# beaconv09.net
KiCad netlist of a schematic drawn in EAGLE
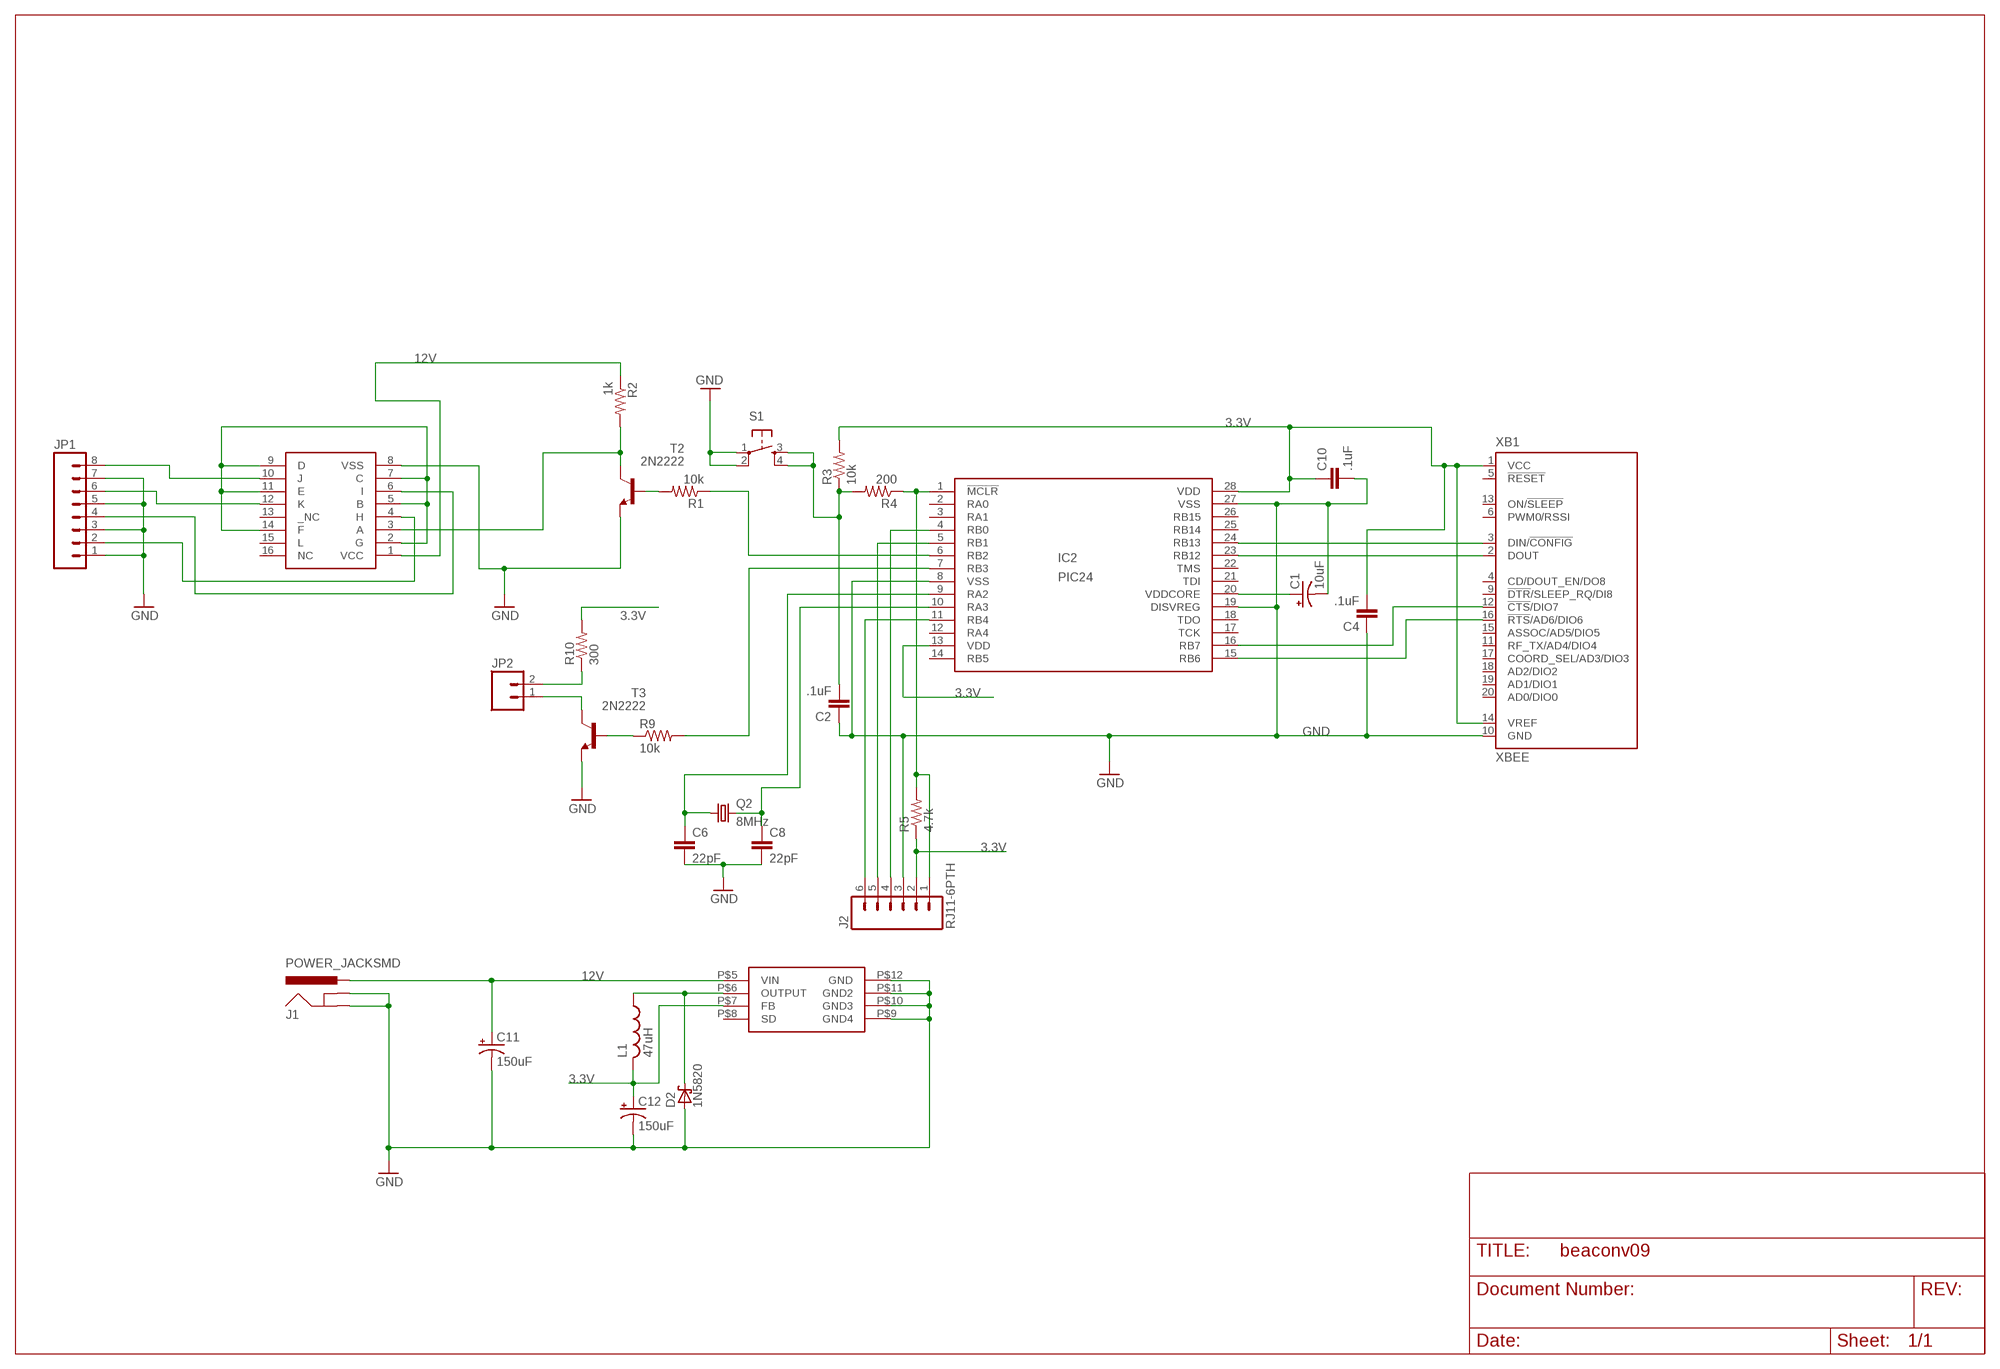
[diagram p0: schematic, sheet 1]

(export (version "E")
  (design (tool "Eeschema 10.0.6"))
  (components
    (comp (ref "AP1509")
      (value "BUCK1")
      (footprint "eagle-import:BUCK")
      (libsource (lib "eagle-import") (part "BUCK1"))
    )
    (comp (ref "C1")
      (value "10uF")
      (footprint "eagle-import:EIA3216")
      (libsource (lib "eagle-import") (part "CAP_POL1206"))
    )
    (comp (ref "C2")
      (value ".1uF")
      (footprint "eagle-import:C1206")
      (libsource (lib "eagle-import") (part "C-EUC1206"))
    )
    (comp (ref "C4")
      (value ".1uF")
      (footprint "eagle-import:C1206")
      (libsource (lib "eagle-import") (part "C-EUC1206"))
    )
    (comp (ref "C6")
      (value "22pF")
      (footprint "eagle-import:C1206")
      (libsource (lib "eagle-import") (part "C-EUC1206"))
    )
    (comp (ref "C8")
      (value "22pF")
      (footprint "eagle-import:C1206")
      (libsource (lib "eagle-import") (part "C-EUC1206"))
    )
    (comp (ref "C10")
      (value ".1uF")
      (footprint "eagle-import:C1206")
      (libsource (lib "eagle-import") (part "C-EUC1206"))
    )
    (comp (ref "C11")
      (value "150uF")
      (footprint "eagle-import:ECAPSMPS")
      (libsource (lib "eagle-import") (part "CAP_POL"))
    )
    (comp (ref "C12")
      (value "150uF")
      (footprint "eagle-import:ECAPSMPS")
      (libsource (lib "eagle-import") (part "CAP_POL"))
    )
    (comp (ref "D2")
      (value "1N5820")
      (footprint "eagle-import:DO201T15")
      (libsource (lib "eagle-import") (part "15KEXXD"))
    )
    (comp (ref "IC2")
      (value "PIC24")
      (footprint "eagle-import:SO28W")
      (libsource (lib "eagle-import") (part "PIC24FJ16GA002"))
    )
    (comp (ref "J1")
      (value "POWER_JACKSMD")
      (footprint "eagle-import:POWER_JACK_SMD")
      (libsource (lib "eagle-import") (part "POWER_JACKSMD"))
    )
    (comp (ref "J2")
      (value "RJ11-6PTH")
      (footprint "eagle-import:RJ11-6")
      (libsource (lib "eagle-import") (part "RJ11-6PTH"))
    )
    (comp (ref "JP1")
      (value "M08LOCK")
      (footprint "eagle-import:1X08_LOCK")
      (libsource (lib "eagle-import") (part "M08LOCK"))
    )
    (comp (ref "JP2")
      (value "M02LOCK")
      (footprint "eagle-import:1X02_LOCK")
      (libsource (lib "eagle-import") (part "M02LOCK"))
    )
    (comp (ref "L1")
      (value "47uH")
      (footprint "eagle-import:BUCKINDUCTOR2")
      (libsource (lib "eagle-import") (part "BUCKINDUCTOR"))
    )
    (comp (ref "Q2")
      (value "8MHz")
      (footprint "eagle-import:HC49UP")
      (libsource (lib "eagle-import") (part "CRYSTALHC49UP"))
    )
    (comp (ref "R1")
      (value "10k")
      (footprint "eagle-import:1206")
      (libsource (lib "eagle-import") (part "RESISTOR1206"))
    )
    (comp (ref "R2")
      (value "1k")
      (footprint "eagle-import:1206")
      (libsource (lib "eagle-import") (part "RESISTOR1206"))
    )
    (comp (ref "R3")
      (value "10k")
      (footprint "eagle-import:1206")
      (libsource (lib "eagle-import") (part "RESISTOR1206"))
    )
    (comp (ref "R4")
      (value "200")
      (footprint "eagle-import:1206")
      (libsource (lib "eagle-import") (part "RESISTOR1206"))
    )
    (comp (ref "R5")
      (value "4.7k")
      (footprint "eagle-import:R1206")
      (libsource (lib "eagle-import") (part "R-US_R1206"))
    )
    (comp (ref "R9")
      (value "10k")
      (footprint "eagle-import:R1206")
      (libsource (lib "eagle-import") (part "R-US_R1206"))
    )
    (comp (ref "R10")
      (value "300")
      (footprint "eagle-import:R1206")
      (libsource (lib "eagle-import") (part "R-US_R1206"))
    )
    (comp (ref "S1")
      (value "TAC_SWITCHSMD")
      (footprint "eagle-import:TACTILE_SWITCH_SMD")
      (libsource (lib "eagle-import") (part "TAC_SWITCHSMD"))
    )
    (comp (ref "T2")
      (value "2N2222")
      (footprint "eagle-import:TO92-CBE")
      (libsource (lib "eagle-import") (part "2N2222"))
    )
    (comp (ref "T3")
      (value "2N2222")
      (footprint "eagle-import:TO92-CBE")
      (libsource (lib "eagle-import") (part "2N2222"))
    )
    (comp (ref "U$2")
      (value "CD4049")
      (footprint "eagle-import:DIL16")
      (libsource (lib "eagle-import") (part "CD4049"))
    )
    (comp (ref "XB1")
      (value "XBEE")
      (footprint "eagle-import:XBEE")
      (fields (field (name "MPN") "XBP24-Z7UIT-004"))
      (libsource (lib "eagle-import") (part "XBEE"))
    )
  )
  (nets
    (net (code "1") (name "/3.3V") (class "Default")
      (node (ref "AP1509") (pin "P$7") (pinfunction "FB_P$7") (pintype "bidirectional"))
      (node (ref "C10") (pin "1") (pinfunction "1_1") (pintype "passive"))
      (node (ref "C12") (pin "P$1") (pinfunction "+_P$1") (pintype "passive"))
      (node (ref "C4") (pin "2") (pinfunction "2_2") (pintype "passive"))
      (node (ref "IC2") (pin "13") (pinfunction "VDD_13") (pintype "power_in"))
      (node (ref "IC2") (pin "28") (pinfunction "VDD_28") (pintype "power_in"))
      (node (ref "J2") (pin "2") (pinfunction "2_2") (pintype "passive"))
      (node (ref "L1") (pin "P$2") (pinfunction "2_P$2") (pintype "passive"))
      (node (ref "R10") (pin "2") (pinfunction "2_2") (pintype "passive"))
      (node (ref "R3") (pin "2") (pinfunction "2_2") (pintype "passive"))
      (node (ref "R5") (pin "1") (pinfunction "1_1") (pintype "passive"))
      (node (ref "XB1") (pin "1") (pinfunction "VCC_1") (pintype "power_in"))
      (node (ref "XB1") (pin "14") (pinfunction "VREF_14") (pintype "input"))
    )
    (net (code "2") (name "/12V") (class "Default")
      (node (ref "AP1509") (pin "P$5") (pinfunction "VIN_P$5") (pintype "bidirectional"))
      (node (ref "C11") (pin "P$1") (pinfunction "+_P$1") (pintype "passive"))
      (node (ref "J1") (pin "VIN0") (pinfunction "PWR_VIN0") (pintype "bidirectional"))
      (node (ref "R2") (pin "1") (pinfunction "1_1") (pintype "passive"))
      (node (ref "U$2") (pin "1") (pinfunction "VCC_1") (pintype "bidirectional"))
    )
    (net (code "3") (name "GND") (class "Default")
      (node (ref "AP1509") (pin "P$10") (pinfunction "GND3_P$10") (pintype "bidirectional"))
      (node (ref "AP1509") (pin "P$11") (pinfunction "GND2_P$11") (pintype "bidirectional"))
      (node (ref "AP1509") (pin "P$12") (pinfunction "GND_P$12") (pintype "bidirectional"))
      (node (ref "AP1509") (pin "P$9") (pinfunction "GND4_P$9") (pintype "bidirectional"))
      (node (ref "C1") (pin "C") (pinfunction "-_C") (pintype "passive"))
      (node (ref "C10") (pin "2") (pinfunction "2_2") (pintype "passive"))
      (node (ref "C11") (pin "P$2") (pinfunction "-_P$2") (pintype "passive"))
      (node (ref "C12") (pin "P$2") (pinfunction "-_P$2") (pintype "passive"))
      (node (ref "C2") (pin "1") (pinfunction "1_1") (pintype "passive"))
      (node (ref "C4") (pin "1") (pinfunction "1_1") (pintype "passive"))
      (node (ref "C6") (pin "2") (pinfunction "2_2") (pintype "passive"))
      (node (ref "C8") (pin "2") (pinfunction "2_2") (pintype "passive"))
      (node (ref "D2") (pin "A") (pinfunction "A_A") (pintype "passive"))
      (node (ref "IC2") (pin "19") (pinfunction "DISVREG_19") (pintype "passive"))
      (node (ref "IC2") (pin "27") (pinfunction "VSS_27") (pintype "power_in"))
      (node (ref "IC2") (pin "8") (pinfunction "VSS_8") (pintype "power_in"))
      (node (ref "J1") (pin "GND") (pinfunction "GNDBREAK_GND") (pintype "bidirectional"))
      (node (ref "J1") (pin "P$4") (pinfunction "GND_P$4") (pintype "bidirectional"))
      (node (ref "J2") (pin "3") (pinfunction "3_3") (pintype "passive"))
      (node (ref "JP1") (pin "1") (pinfunction "1_1") (pintype "passive"))
      (node (ref "JP1") (pin "3") (pinfunction "3_3") (pintype "passive"))
      (node (ref "JP1") (pin "5") (pinfunction "5_5") (pintype "passive"))
      (node (ref "JP1") (pin "7") (pinfunction "7_7") (pintype "passive"))
      (node (ref "S1") (pin "1") (pinfunction "1_1") (pintype "passive"))
      (node (ref "S1") (pin "2") (pinfunction "2_2") (pintype "passive"))
      (node (ref "T2") (pin "E") (pinfunction "E_E") (pintype "passive"))
      (node (ref "T3") (pin "E") (pinfunction "E_E") (pintype "passive"))
      (node (ref "U$2") (pin "8") (pinfunction "VSS_8") (pintype "bidirectional"))
      (node (ref "XB1") (pin "10") (pinfunction "GND_10") (pintype "power_in"))
    )
    (net (code "4") (name "Net-(AP1509-OUTPUT)") (class "Default")
      (node (ref "AP1509") (pin "P$6") (pinfunction "OUTPUT_P$6") (pintype "bidirectional"))
      (node (ref "D2") (pin "C") (pinfunction "C_C") (pintype "passive"))
      (node (ref "L1") (pin "P$1") (pinfunction "1_P$1") (pintype "passive"))
    )
    (net (code "5") (name "Net-(C1-+)") (class "Default")
      (node (ref "C1") (pin "A") (pinfunction "+_A") (pintype "passive"))
      (node (ref "IC2") (pin "20") (pinfunction "VDDCORE_20") (pintype "power_in"))
    )
    (net (code "6") (name "Net-(C2-Pad2)") (class "Default")
      (node (ref "C2") (pin "2") (pinfunction "2_2") (pintype "passive"))
      (node (ref "R3") (pin "1") (pinfunction "1_1") (pintype "passive"))
      (node (ref "R4") (pin "2") (pinfunction "2_2") (pintype "passive"))
      (node (ref "S1") (pin "3") (pinfunction "3_3") (pintype "passive"))
      (node (ref "S1") (pin "4") (pinfunction "4_4") (pintype "passive"))
    )
    (net (code "7") (name "Net-(IC2-RA2)") (class "Default")
      (node (ref "C6") (pin "1") (pinfunction "1_1") (pintype "passive"))
      (node (ref "IC2") (pin "9") (pinfunction "RA2_9") (pintype "bidirectional"))
      (node (ref "Q2") (pin "1") (pinfunction "1_1") (pintype "passive"))
    )
    (net (code "8") (name "Net-(IC2-RA3)") (class "Default")
      (node (ref "C8") (pin "1") (pinfunction "1_1") (pintype "passive"))
      (node (ref "IC2") (pin "10") (pinfunction "RA3_10") (pintype "bidirectional"))
      (node (ref "Q2") (pin "2") (pinfunction "2_2") (pintype "passive"))
    )
    (net (code "9") (name "Net-(IC2-RB0)") (class "Default")
      (node (ref "IC2") (pin "4") (pinfunction "RB0_4") (pintype "bidirectional"))
      (node (ref "J2") (pin "4") (pinfunction "4_4") (pintype "passive"))
    )
    (net (code "10") (name "Net-(IC2-RB1)") (class "Default")
      (node (ref "IC2") (pin "5") (pinfunction "RB1_5") (pintype "bidirectional"))
      (node (ref "J2") (pin "5") (pinfunction "5_5") (pintype "passive"))
    )
    (net (code "11") (name "Net-(IC2-RB2)") (class "Default")
      (node (ref "IC2") (pin "6") (pinfunction "RB2_6") (pintype "bidirectional"))
      (node (ref "R1") (pin "1") (pinfunction "1_1") (pintype "passive"))
    )
    (net (code "12") (name "Net-(IC2-RB3)") (class "Default")
      (node (ref "IC2") (pin "7") (pinfunction "RB3_7") (pintype "bidirectional"))
      (node (ref "R9") (pin "2") (pinfunction "2_2") (pintype "passive"))
    )
    (net (code "13") (name "Net-(IC2-RB4)") (class "Default")
      (node (ref "IC2") (pin "11") (pinfunction "RB4_11") (pintype "bidirectional"))
      (node (ref "J2") (pin "6") (pinfunction "6_6") (pintype "passive"))
    )
    (net (code "14") (name "Net-(IC2-RB6)") (class "Default")
      (node (ref "IC2") (pin "15") (pinfunction "RB6_15") (pintype "bidirectional"))
      (node (ref "XB1") (pin "16") (pinfunction "~{RTS}/AD6/DIO6_16") (pintype "bidirectional"))
    )
    (net (code "15") (name "Net-(IC2-RB7)") (class "Default")
      (node (ref "IC2") (pin "16") (pinfunction "RB7_16") (pintype "bidirectional"))
      (node (ref "XB1") (pin "12") (pinfunction "~{CTS}/DIO7_12") (pintype "bidirectional"))
    )
    (net (code "16") (name "Net-(IC2-RB12)") (class "Default")
      (node (ref "IC2") (pin "23") (pinfunction "RB12_23") (pintype "bidirectional"))
      (node (ref "XB1") (pin "2") (pinfunction "DOUT_2") (pintype "output"))
    )
    (net (code "17") (name "Net-(IC2-RB13)") (class "Default")
      (node (ref "IC2") (pin "24") (pinfunction "RB13_24") (pintype "bidirectional"))
      (node (ref "XB1") (pin "3") (pinfunction "DIN/~{CONFIG}_3") (pintype "input"))
    )
    (net (code "18") (name "Net-(IC2-~{MCLR})") (class "Default")
      (node (ref "IC2") (pin "1") (pinfunction "~{MCLR}_1") (pintype "bidirectional"))
      (node (ref "J2") (pin "1") (pinfunction "1_1") (pintype "passive"))
      (node (ref "R4") (pin "1") (pinfunction "1_1") (pintype "passive"))
      (node (ref "R5") (pin "2") (pinfunction "2_2") (pintype "passive"))
    )
    (net (code "19") (name "Net-(JP2-Pad1)") (class "Default")
      (node (ref "JP2") (pin "1") (pinfunction "1_1") (pintype "passive"))
      (node (ref "T3") (pin "C") (pinfunction "C_C") (pintype "passive"))
    )
    (net (code "20") (name "Net-(JP2-Pad2)") (class "Default")
      (node (ref "JP2") (pin "2") (pinfunction "2_2") (pintype "passive"))
      (node (ref "R10") (pin "1") (pinfunction "1_1") (pintype "passive"))
    )
    (net (code "21") (name "Net-(R1-Pad2)") (class "Default")
      (node (ref "R1") (pin "2") (pinfunction "2_2") (pintype "passive"))
      (node (ref "T2") (pin "B") (pinfunction "B_B") (pintype "passive"))
    )
    (net (code "22") (name "Net-(R9-Pad1)") (class "Default")
      (node (ref "R9") (pin "1") (pinfunction "1_1") (pintype "passive"))
      (node (ref "T3") (pin "B") (pinfunction "B_B") (pintype "passive"))
    )
    (net (code "23") (name "Net-(U$2-A)") (class "Default")
      (node (ref "R2") (pin "2") (pinfunction "2_2") (pintype "passive"))
      (node (ref "T2") (pin "C") (pinfunction "C_C") (pintype "passive"))
      (node (ref "U$2") (pin "3") (pinfunction "A_3") (pintype "bidirectional"))
    )
    (net (code "24") (name "Net-(U$2-B)") (class "Default")
      (node (ref "U$2") (pin "11") (pinfunction "E_11") (pintype "bidirectional"))
      (node (ref "U$2") (pin "14") (pinfunction "F_14") (pintype "bidirectional"))
      (node (ref "U$2") (pin "2") (pinfunction "G_2") (pintype "bidirectional"))
      (node (ref "U$2") (pin "5") (pinfunction "B_5") (pintype "bidirectional"))
      (node (ref "U$2") (pin "7") (pinfunction "C_7") (pintype "bidirectional"))
      (node (ref "U$2") (pin "9") (pinfunction "D_9") (pintype "bidirectional"))
    )
    (net (code "25") (name "Net-(U$2-H)") (class "Default")
      (node (ref "JP1") (pin "2") (pinfunction "2_2") (pintype "passive"))
      (node (ref "U$2") (pin "4") (pinfunction "H_4") (pintype "bidirectional"))
    )
    (net (code "26") (name "Net-(U$2-I)") (class "Default")
      (node (ref "JP1") (pin "4") (pinfunction "4_4") (pintype "passive"))
      (node (ref "U$2") (pin "6") (pinfunction "I_6") (pintype "bidirectional"))
    )
    (net (code "27") (name "Net-(U$2-J)") (class "Default")
      (node (ref "JP1") (pin "8") (pinfunction "8_8") (pintype "passive"))
      (node (ref "U$2") (pin "10") (pinfunction "J_10") (pintype "bidirectional"))
    )
    (net (code "28") (name "Net-(U$2-K)") (class "Default")
      (node (ref "JP1") (pin "6") (pinfunction "6_6") (pintype "passive"))
      (node (ref "U$2") (pin "12") (pinfunction "K_12") (pintype "bidirectional"))
    )
    (net (code "29") (name "unconnected-(AP1509-SD-PadP$8)") (class "Default")
      (node (ref "AP1509") (pin "P$8") (pinfunction "SD_P$8") (pintype "bidirectional"))
    )
    (net (code "30") (name "unconnected-(IC2-RA0-Pad2)") (class "Default")
      (node (ref "IC2") (pin "2") (pinfunction "RA0_2") (pintype "bidirectional"))
    )
    (net (code "31") (name "unconnected-(IC2-RA1-Pad3)") (class "Default")
      (node (ref "IC2") (pin "3") (pinfunction "RA1_3") (pintype "bidirectional"))
    )
    (net (code "32") (name "unconnected-(IC2-RA4-Pad12)") (class "Default")
      (node (ref "IC2") (pin "12") (pinfunction "RA4_12") (pintype "bidirectional"))
    )
    (net (code "33") (name "unconnected-(IC2-RB5-Pad14)") (class "Default")
      (node (ref "IC2") (pin "14") (pinfunction "RB5_14") (pintype "bidirectional"))
    )
    (net (code "34") (name "unconnected-(IC2-RB14-Pad25)") (class "Default")
      (node (ref "IC2") (pin "25") (pinfunction "RB14_25") (pintype "bidirectional"))
    )
    (net (code "35") (name "unconnected-(IC2-RB15-Pad26)") (class "Default")
      (node (ref "IC2") (pin "26") (pinfunction "RB15_26") (pintype "bidirectional"))
    )
    (net (code "36") (name "unconnected-(IC2-TCK-Pad17)") (class "Default")
      (node (ref "IC2") (pin "17") (pinfunction "TCK_17") (pintype "input"))
    )
    (net (code "37") (name "unconnected-(IC2-TDI-Pad21)") (class "Default")
      (node (ref "IC2") (pin "21") (pinfunction "TDI_21") (pintype "input"))
    )
    (net (code "38") (name "unconnected-(IC2-TDO-Pad18)") (class "Default")
      (node (ref "IC2") (pin "18") (pinfunction "TDO_18") (pintype "output"))
    )
    (net (code "39") (name "unconnected-(IC2-TMS-Pad22)") (class "Default")
      (node (ref "IC2") (pin "22") (pinfunction "TMS_22") (pintype "input"))
    )
    (net (code "40") (name "unconnected-(U$2-L-Pad15)") (class "Default")
      (node (ref "U$2") (pin "15") (pinfunction "L_15") (pintype "bidirectional"))
    )
    (net (code "41") (name "unconnected-(U$2-NC-Pad16)") (class "Default")
      (node (ref "U$2") (pin "16") (pinfunction "NC_16") (pintype "bidirectional"))
    )
    (net (code "42") (name "unconnected-(U$2-_NC-Pad13)") (class "Default")
      (node (ref "U$2") (pin "13") (pinfunction "_NC_13") (pintype "bidirectional"))
    )
    (net (code "43") (name "unconnected-(XB1-AD0{slash}DIO0-Pad20)") (class "Default")
      (node (ref "XB1") (pin "20") (pinfunction "AD0/DIO0_20") (pintype "bidirectional"))
    )
    (net (code "44") (name "unconnected-(XB1-AD1{slash}DIO1-Pad19)") (class "Default")
      (node (ref "XB1") (pin "19") (pinfunction "AD1/DIO1_19") (pintype "bidirectional"))
    )
    (net (code "45") (name "unconnected-(XB1-AD2{slash}DIO2-Pad18)") (class "Default")
      (node (ref "XB1") (pin "18") (pinfunction "AD2/DIO2_18") (pintype "bidirectional"))
    )
    (net (code "46") (name "unconnected-(XB1-ASSOC{slash}AD5{slash}DIO5-Pad15)") (class "Default")
      (node (ref "XB1") (pin "15") (pinfunction "ASSOC/AD5/DIO5_15") (pintype "bidirectional"))
    )
    (net (code "47") (name "unconnected-(XB1-CD{slash}DOUT_EN{slash}DO8-Pad4)") (class "Default")
      (node (ref "XB1") (pin "4") (pinfunction "CD/DOUT_EN/DO8_4") (pintype "output"))
    )
    (net (code "48") (name "unconnected-(XB1-COORD_SEL{slash}AD3{slash}DIO3-Pad17)") (class "Default")
      (node (ref "XB1") (pin "17") (pinfunction "COORD_SEL/AD3/DIO3_17") (pintype "bidirectional"))
    )
    (net (code "49") (name "unconnected-(XB1-ON{slash}~{SLEEP}-Pad13)") (class "Default")
      (node (ref "XB1") (pin "13") (pinfunction "ON/~{SLEEP}_13") (pintype "output"))
    )
    (net (code "50") (name "unconnected-(XB1-PWM0{slash}RSSI-Pad6)") (class "Default")
      (node (ref "XB1") (pin "6") (pinfunction "PWM0/RSSI_6") (pintype "output"))
    )
    (net (code "51") (name "unconnected-(XB1-RF_TX{slash}AD4{slash}DIO4-Pad11)") (class "Default")
      (node (ref "XB1") (pin "11") (pinfunction "RF_TX/AD4/DIO4_11") (pintype "bidirectional"))
    )
    (net (code "52") (name "unconnected-(XB1-~{DTR}{slash}SLEEP_RQ{slash}DI8-Pad9)") (class "Default")
      (node (ref "XB1") (pin "9") (pinfunction "~{DTR}/SLEEP_RQ/DI8_9") (pintype "bidirectional"))
    )
    (net (code "53") (name "unconnected-(XB1-~{RESET}-Pad5)") (class "Default")
      (node (ref "XB1") (pin "5") (pinfunction "~{RESET}_5") (pintype "input"))
    )
  )
)
